# design.net
KiCad netlist of a schematic drawn in Altium Designer
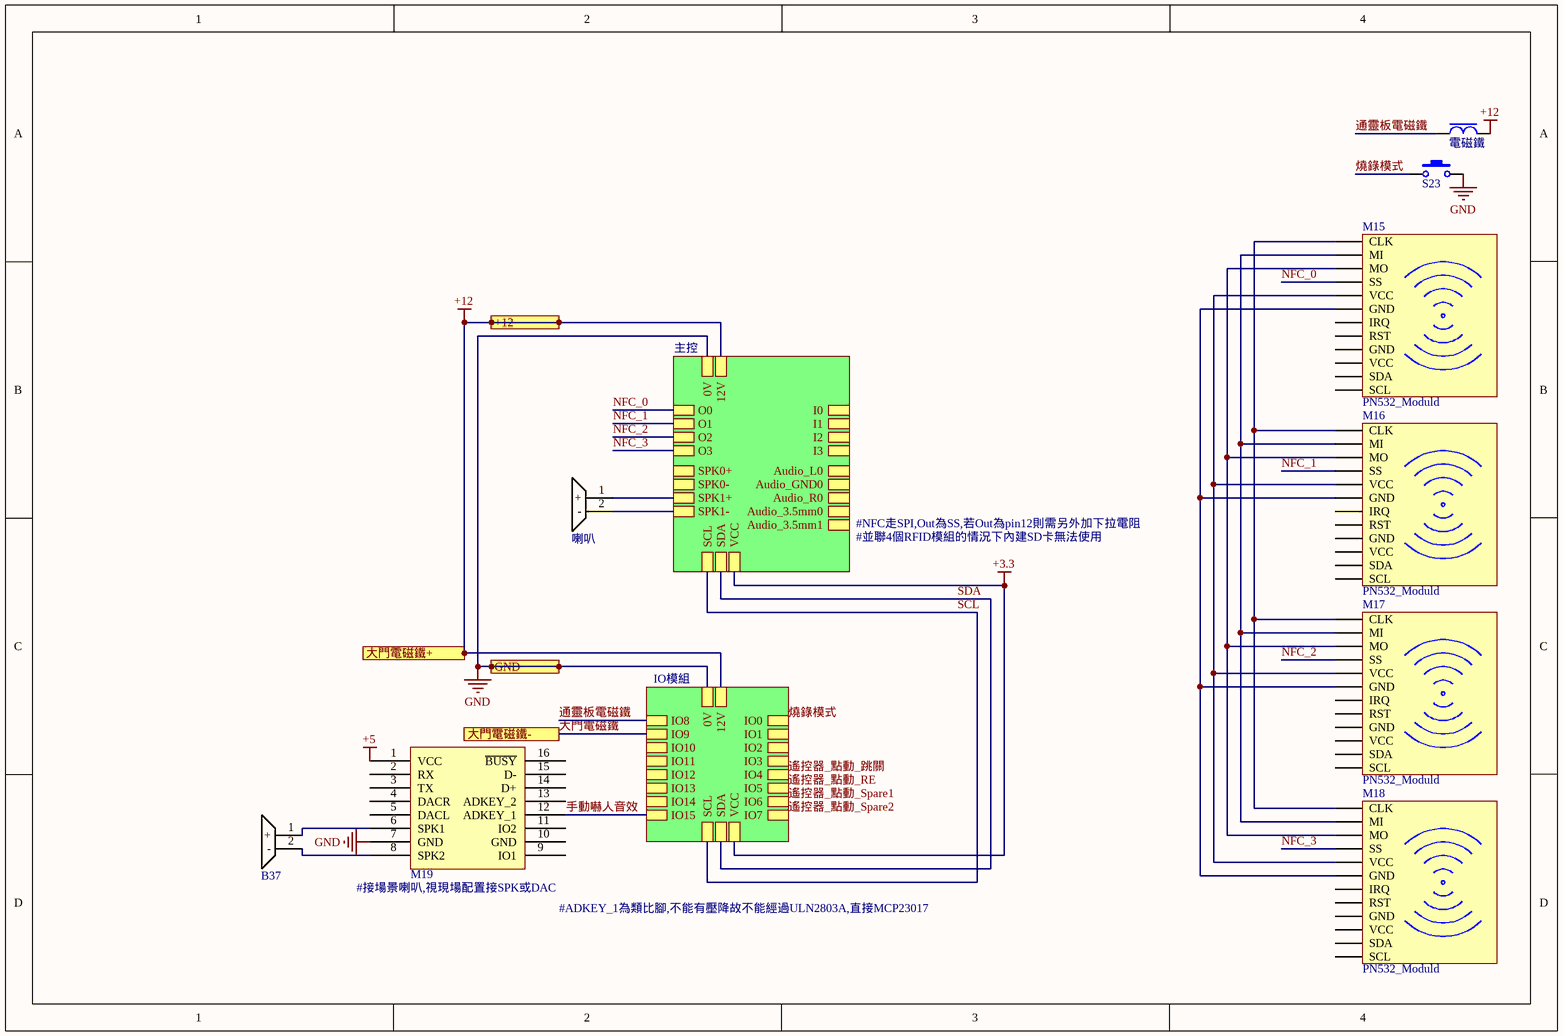
[diagram p0: 松菸_幻影光靈_屍禁_通靈板.SchDoc]

(export (version "E")
  (design (tool "Eeschema 10.0.6"))
  (components
    (comp (ref "B34")
      (value "喇叭")
      (footprint "Buzzer_12085")
      (description "無源蜂鳴器")
      (libsource (lib "MyLibray") (part "Buzzer"))
    )
    (comp (ref "B37")
      (value "FMB1275-05")
      (footprint "Buzzer_12085")
      (description "無源蜂鳴器")
      (libsource (lib "MyLibray") (part "Buzzer"))
    )
    (comp (ref "I8")
      (value "電磁鐵")
      (footprint "Inductor-0420")
      (description "一體成型電感")
      (libsource (lib "MyLibray") (part "Inductor"))
    )
    (comp (ref "M15")
      (value "PN532_Moduld")
      (footprint "PN532")
      (description "NFC模組")
      (libsource (lib "MyLibray") (part "PN532_Moduld"))
    )
    (comp (ref "M16")
      (value "PN532_Moduld")
      (footprint "PN532")
      (description "NFC模組")
      (libsource (lib "MyLibray") (part "PN532_Moduld"))
    )
    (comp (ref "M17")
      (value "PN532_Moduld")
      (footprint "PN532")
      (description "NFC模組")
      (libsource (lib "MyLibray") (part "PN532_Moduld"))
    )
    (comp (ref "M18")
      (value "PN532_Moduld")
      (footprint "PN532")
      (description "NFC模組")
      (libsource (lib "MyLibray") (part "PN532_Moduld"))
    )
    (comp (ref "M19")
      (value "BY8001-16P")
      (footprint "BY8001-16P")
      (description "TTL通訊SD卡撥放mp3模組")
      (libsource (lib "MyLibray") (part "Mini MP3 Player"))
    )
    (comp (ref "S23")
      (value "Switch")
      (footprint "Switch SMD-3.6*6*2.5")
      (description "開關_按鍵")
      (libsource (lib "MyLibray") (part "Switch"))
    )
  )
  (nets
    (net (code "2") (name "+5") (class "Default")
      (node (ref "M19") (pin "1") (pinfunction "VCC_1") (pintype "passive"))
    )
    (net (code "3") (name "+12") (class "Default")
      (node (ref "I8") (pin "2") (pinfunction "2_2") (pintype "passive"))
    )
    (net (code "21") (name "/NFC_0") (class "Default")
      (node (ref "M15") (pin "4") (pinfunction "SS_4") (pintype "passive"))
    )
    (net (code "22") (name "/NFC_1") (class "Default")
      (node (ref "M16") (pin "4") (pinfunction "SS_4") (pintype "passive"))
    )
    (net (code "23") (name "/NFC_2") (class "Default")
      (node (ref "M17") (pin "4") (pinfunction "SS_4") (pintype "passive"))
    )
    (net (code "24") (name "/NFC_3") (class "Default")
      (node (ref "M18") (pin "4") (pinfunction "SS_4") (pintype "passive"))
    )
    (net (code "29") (name "/SPK1+") (class "Default")
      (node (ref "B34") (pin "1") (pinfunction "+_1") (pintype "passive"))
    )
    (net (code "30") (name "/SPK1-") (class "Default")
      (node (ref "B34") (pin "2") (pinfunction "-_2") (pintype "passive"))
    )
    (net (code "32") (name "/手動嚇人音效") (class "Default")
      (node (ref "M19") (pin "12") (pinfunction "ADKEY_1_12") (pintype "passive"))
    )
    (net (code "33") (name "/燒錄模式") (class "Default")
      (node (ref "S23") (pin "1") (pinfunction "1_1") (pintype "passive"))
    )
    (net (code "34") (name "/通靈板電磁鐵") (class "Default")
      (node (ref "I8") (pin "1") (pinfunction "1_1") (pintype "passive"))
    )
    (net (code "39") (name "GND") (class "Default")
      (node (ref "M19") (pin "7") (pinfunction "GND_7") (pintype "passive"))
      (node (ref "S23") (pin "2") (pinfunction "2_2") (pintype "passive"))
    )
    (net (code "40") (name "Net-(B37-+)") (class "Default")
      (node (ref "B37") (pin "1") (pinfunction "+_1") (pintype "passive"))
      (node (ref "M19") (pin "6") (pinfunction "SPK1_6") (pintype "passive"))
    )
    (net (code "41") (name "Net-(B37--)") (class "Default")
      (node (ref "B37") (pin "2") (pinfunction "-_2") (pintype "passive"))
      (node (ref "M19") (pin "8") (pinfunction "SPK2_8") (pintype "passive"))
    )
    (net (code "42") (name "Net-(M15-CLK)") (class "Default")
      (node (ref "M15") (pin "1") (pinfunction "CLK_1") (pintype "passive"))
      (node (ref "M16") (pin "1") (pinfunction "CLK_1") (pintype "passive"))
      (node (ref "M17") (pin "1") (pinfunction "CLK_1") (pintype "passive"))
      (node (ref "M18") (pin "1") (pinfunction "CLK_1") (pintype "passive"))
    )
    (net (code "43") (name "Net-(M15-GND-Pad6)") (class "Default")
      (node (ref "M15") (pin "6") (pinfunction "GND_6") (pintype "passive"))
      (node (ref "M16") (pin "6") (pinfunction "GND_6") (pintype "passive"))
      (node (ref "M17") (pin "6") (pinfunction "GND_6") (pintype "passive"))
      (node (ref "M18") (pin "6") (pinfunction "GND_6") (pintype "passive"))
    )
    (net (code "44") (name "Net-(M15-MI)") (class "Default")
      (node (ref "M15") (pin "2") (pinfunction "MI_2") (pintype "passive"))
      (node (ref "M16") (pin "2") (pinfunction "MI_2") (pintype "passive"))
      (node (ref "M17") (pin "2") (pinfunction "MI_2") (pintype "passive"))
      (node (ref "M18") (pin "2") (pinfunction "MI_2") (pintype "passive"))
    )
    (net (code "45") (name "Net-(M15-MO)") (class "Default")
      (node (ref "M15") (pin "3") (pinfunction "MO_3") (pintype "passive"))
      (node (ref "M16") (pin "3") (pinfunction "MO_3") (pintype "passive"))
      (node (ref "M17") (pin "3") (pinfunction "MO_3") (pintype "passive"))
      (node (ref "M18") (pin "3") (pinfunction "MO_3") (pintype "passive"))
    )
    (net (code "46") (name "Net-(M15-VCC-Pad5)") (class "Default")
      (node (ref "M15") (pin "5") (pinfunction "VCC_5") (pintype "passive"))
      (node (ref "M16") (pin "5") (pinfunction "VCC_5") (pintype "passive"))
      (node (ref "M17") (pin "5") (pinfunction "VCC_5") (pintype "passive"))
      (node (ref "M18") (pin "5") (pinfunction "VCC_5") (pintype "passive"))
    )
    (net (code "47") (name "unconnected-(M15-GND-Pad9)") (class "Default")
      (node (ref "M15") (pin "9") (pinfunction "GND_9") (pintype "passive"))
    )
    (net (code "48") (name "unconnected-(M15-IRQ-Pad7)") (class "Default")
      (node (ref "M15") (pin "7") (pinfunction "IRQ_7") (pintype "passive"))
    )
    (net (code "49") (name "unconnected-(M15-RST-Pad8)") (class "Default")
      (node (ref "M15") (pin "8") (pinfunction "RST_8") (pintype "passive"))
    )
    (net (code "50") (name "unconnected-(M15-SCL-Pad12)") (class "Default")
      (node (ref "M15") (pin "12") (pinfunction "SCL_12") (pintype "passive"))
    )
    (net (code "51") (name "unconnected-(M15-SDA-Pad11)") (class "Default")
      (node (ref "M15") (pin "11") (pinfunction "SDA_11") (pintype "passive"))
    )
    (net (code "52") (name "unconnected-(M15-VCC-Pad10)") (class "Default")
      (node (ref "M15") (pin "10") (pinfunction "VCC_10") (pintype "passive"))
    )
    (net (code "53") (name "unconnected-(M16-GND-Pad9)") (class "Default")
      (node (ref "M16") (pin "9") (pinfunction "GND_9") (pintype "passive"))
    )
    (net (code "54") (name "unconnected-(M16-IRQ-Pad7)") (class "Default")
      (node (ref "M16") (pin "7") (pinfunction "IRQ_7") (pintype "passive"))
    )
    (net (code "55") (name "unconnected-(M16-RST-Pad8)") (class "Default")
      (node (ref "M16") (pin "8") (pinfunction "RST_8") (pintype "passive"))
    )
    (net (code "56") (name "unconnected-(M16-SCL-Pad12)") (class "Default")
      (node (ref "M16") (pin "12") (pinfunction "SCL_12") (pintype "passive"))
    )
    (net (code "57") (name "unconnected-(M16-SDA-Pad11)") (class "Default")
      (node (ref "M16") (pin "11") (pinfunction "SDA_11") (pintype "passive"))
    )
    (net (code "58") (name "unconnected-(M16-VCC-Pad10)") (class "Default")
      (node (ref "M16") (pin "10") (pinfunction "VCC_10") (pintype "passive"))
    )
    (net (code "59") (name "unconnected-(M17-GND-Pad9)") (class "Default")
      (node (ref "M17") (pin "9") (pinfunction "GND_9") (pintype "passive"))
    )
    (net (code "60") (name "unconnected-(M17-IRQ-Pad7)") (class "Default")
      (node (ref "M17") (pin "7") (pinfunction "IRQ_7") (pintype "passive"))
    )
    (net (code "61") (name "unconnected-(M17-RST-Pad8)") (class "Default")
      (node (ref "M17") (pin "8") (pinfunction "RST_8") (pintype "passive"))
    )
    (net (code "62") (name "unconnected-(M17-SCL-Pad12)") (class "Default")
      (node (ref "M17") (pin "12") (pinfunction "SCL_12") (pintype "passive"))
    )
    (net (code "63") (name "unconnected-(M17-SDA-Pad11)") (class "Default")
      (node (ref "M17") (pin "11") (pinfunction "SDA_11") (pintype "passive"))
    )
    (net (code "64") (name "unconnected-(M17-VCC-Pad10)") (class "Default")
      (node (ref "M17") (pin "10") (pinfunction "VCC_10") (pintype "passive"))
    )
    (net (code "65") (name "unconnected-(M18-GND-Pad9)") (class "Default")
      (node (ref "M18") (pin "9") (pinfunction "GND_9") (pintype "passive"))
    )
    (net (code "66") (name "unconnected-(M18-IRQ-Pad7)") (class "Default")
      (node (ref "M18") (pin "7") (pinfunction "IRQ_7") (pintype "passive"))
    )
    (net (code "67") (name "unconnected-(M18-RST-Pad8)") (class "Default")
      (node (ref "M18") (pin "8") (pinfunction "RST_8") (pintype "passive"))
    )
    (net (code "68") (name "unconnected-(M18-SCL-Pad12)") (class "Default")
      (node (ref "M18") (pin "12") (pinfunction "SCL_12") (pintype "passive"))
    )
    (net (code "69") (name "unconnected-(M18-SDA-Pad11)") (class "Default")
      (node (ref "M18") (pin "11") (pinfunction "SDA_11") (pintype "passive"))
    )
    (net (code "70") (name "unconnected-(M18-VCC-Pad10)") (class "Default")
      (node (ref "M18") (pin "10") (pinfunction "VCC_10") (pintype "passive"))
    )
    (net (code "71") (name "unconnected-(M19-ADKEY_2-Pad13)") (class "Default")
      (node (ref "M19") (pin "13") (pinfunction "ADKEY_2_13") (pintype "passive"))
    )
    (net (code "72") (name "unconnected-(M19-D+-Pad14)") (class "Default")
      (node (ref "M19") (pin "14") (pinfunction "D+_14") (pintype "passive"))
    )
    (net (code "73") (name "unconnected-(M19-D--Pad15)") (class "Default")
      (node (ref "M19") (pin "15") (pinfunction "D-_15") (pintype "passive"))
    )
    (net (code "74") (name "unconnected-(M19-DACL-Pad5)") (class "Default")
      (node (ref "M19") (pin "5") (pinfunction "DACL_5") (pintype "passive"))
    )
    (net (code "75") (name "unconnected-(M19-DACR-Pad4)") (class "Default")
      (node (ref "M19") (pin "4") (pinfunction "DACR_4") (pintype "passive"))
    )
    (net (code "76") (name "unconnected-(M19-GND-Pad10)") (class "Default")
      (node (ref "M19") (pin "10") (pinfunction "GND_10") (pintype "passive"))
    )
    (net (code "77") (name "unconnected-(M19-IO1-Pad9)") (class "Default")
      (node (ref "M19") (pin "9") (pinfunction "IO1_9") (pintype "passive"))
    )
    (net (code "78") (name "unconnected-(M19-IO2-Pad11)") (class "Default")
      (node (ref "M19") (pin "11") (pinfunction "IO2_11") (pintype "passive"))
    )
    (net (code "79") (name "unconnected-(M19-RX-Pad2)") (class "Default")
      (node (ref "M19") (pin "2") (pinfunction "RX_2") (pintype "passive"))
    )
    (net (code "80") (name "unconnected-(M19-TX-Pad3)") (class "Default")
      (node (ref "M19") (pin "3") (pinfunction "TX_3") (pintype "passive"))
    )
    (net (code "81") (name "unconnected-(M19-~{BUSY}-Pad16)") (class "Default")
      (node (ref "M19") (pin "16") (pinfunction "~{BUSY}_16") (pintype "passive"))
    )
  )
)
